# SVmitTreiber3LED2.net
KiCad netlist of a schematic drawn in EAGLE
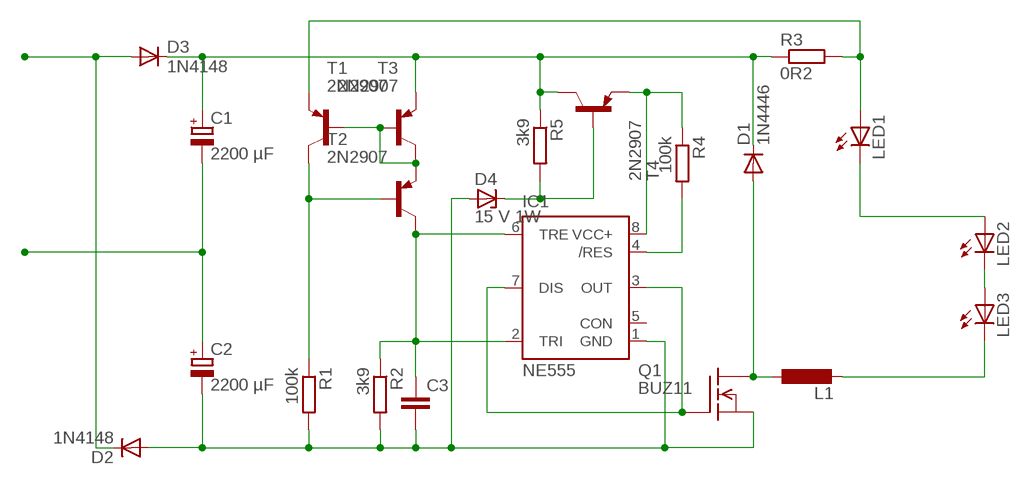
[diagram p0: schematic, sheet 1]

(export (version "E")
  (design (tool "Eeschema 10.0.6"))
  (components
    (comp (ref "C1")
      (value "2200 µF")
      (footprint "eagle-import:E5-10,5")
      (libsource (lib "eagle-import") (part "CPOL-EUE5-10.5"))
    )
    (comp (ref "C2")
      (value "2200 µF")
      (footprint "eagle-import:E5-10,5")
      (libsource (lib "eagle-import") (part "CPOL-EUE5-10.5"))
    )
    (comp (ref "C3")
      (value "C-EU025-024X044")
      (footprint "eagle-import:C025-024X044")
      (libsource (lib "eagle-import") (part "C-EU025-024X044"))
    )
    (comp (ref "D1")
      (value "1N4446")
      (footprint "eagle-import:DO35-10")
      (libsource (lib "eagle-import") (part "1N4446"))
    )
    (comp (ref "D2")
      (value "1N4148")
      (footprint "eagle-import:DO35-10")
      (libsource (lib "eagle-import") (part "1N4148DO35-10"))
    )
    (comp (ref "D3")
      (value "1N4148")
      (footprint "eagle-import:DO35-10")
      (libsource (lib "eagle-import") (part "1N4148DO35-10"))
    )
    (comp (ref "D4")
      (value "15 V 1W")
      (footprint "eagle-import:DO41Z10")
      (libsource (lib "eagle-import") (part "1N4728"))
    )
    (comp (ref "IC1")
      (value "NE555")
      (footprint "eagle-import:DIL-08")
      (fields (field (name "MF") "Arrow Electronics") (field (name "MPN") "NE555N"))
      (libsource (lib "eagle-import") (part "NE555"))
    )
    (comp (ref "L1")
      (value "L-EU6000-XXX-RC")
      (footprint "eagle-import:6000-XXXX-RC")
      (libsource (lib "eagle-import") (part "L-EU6000-XXX-RC"))
    )
    (comp (ref "LED1")
      (value "LED10MM")
      (footprint "eagle-import:LED10MM")
      (libsource (lib "eagle-import") (part "LED10MM"))
    )
    (comp (ref "LED2")
      (value "LED10MM")
      (footprint "eagle-import:LED10MM")
      (libsource (lib "eagle-import") (part "LED10MM"))
    )
    (comp (ref "LED3")
      (value "LED10MM")
      (footprint "eagle-import:LED10MM")
      (libsource (lib "eagle-import") (part "LED10MM"))
    )
    (comp (ref "Q1")
      (value "BUZ11")
      (footprint "eagle-import:TO220")
      (libsource (lib "eagle-import") (part "BUZ11"))
    )
    (comp (ref "R1")
      (value "100k")
      (footprint "eagle-import:0207_10")
      (libsource (lib "eagle-import") (part "R-EU_0207/10"))
    )
    (comp (ref "R2")
      (value "3k9")
      (footprint "eagle-import:0207_10")
      (libsource (lib "eagle-import") (part "R-EU_0207/10"))
    )
    (comp (ref "R3")
      (value "0R2")
      (footprint "eagle-import:0207_15")
      (libsource (lib "eagle-import") (part "R-EU_0207/15"))
    )
    (comp (ref "R4")
      (value "100k")
      (footprint "eagle-import:0207_10")
      (libsource (lib "eagle-import") (part "R-EU_0207/10"))
    )
    (comp (ref "R5")
      (value "3k9")
      (footprint "eagle-import:0207_10")
      (libsource (lib "eagle-import") (part "R-EU_0207/10"))
    )
    (comp (ref "T1")
      (value "2N2907")
      (footprint "eagle-import:TO18")
      (libsource (lib "eagle-import") (part "2N2907"))
    )
    (comp (ref "T2")
      (value "2N2907")
      (footprint "eagle-import:TO18")
      (libsource (lib "eagle-import") (part "2N2907"))
    )
    (comp (ref "T3")
      (value "2N2907")
      (footprint "eagle-import:TO18")
      (libsource (lib "eagle-import") (part "2N2907"))
    )
    (comp (ref "T4")
      (value "2N2907")
      (footprint "eagle-import:TO18")
      (libsource (lib "eagle-import") (part "2N2907"))
    )
  )
  (nets
    (net (code "1") (name "Net-(C1-Pad-)") (class "Default")
      (node (ref "C1") (pin "-") (pinfunction "-_-") (pintype "passive"))
      (node (ref "C2") (pin "+") (pinfunction "+_+") (pintype "passive"))
    )
    (net (code "2") (name "Net-(D2-PadC)") (class "Default")
      (node (ref "D2") (pin "C") (pinfunction "C_C") (pintype "passive"))
      (node (ref "D3") (pin "A") (pinfunction "A_A") (pintype "passive"))
    )
    (net (code "3") (name "Net-(IC1-DIS)") (class "Default")
      (node (ref "IC1") (pin "3") (pinfunction "OUT_3") (pintype "output"))
      (node (ref "IC1") (pin "7") (pinfunction "DIS_7") (pintype "input"))
      (node (ref "Q1") (pin "1") (pinfunction "G_1") (pintype "passive"))
    )
    (net (code "4") (name "Net-(IC1-GND)") (class "Default")
      (node (ref "C2") (pin "-") (pinfunction "-_-") (pintype "passive"))
      (node (ref "C3") (pin "2") (pinfunction "2_2") (pintype "passive"))
      (node (ref "D2") (pin "A") (pinfunction "A_A") (pintype "passive"))
      (node (ref "D4") (pin "A") (pinfunction "A_A") (pintype "passive"))
      (node (ref "IC1") (pin "1") (pinfunction "GND_1") (pintype "power_in"))
      (node (ref "Q1") (pin "3") (pinfunction "S_3") (pintype "passive"))
      (node (ref "R1") (pin "2") (pinfunction "2_2") (pintype "passive"))
      (node (ref "R2") (pin "2") (pinfunction "2_2") (pintype "passive"))
    )
    (net (code "5") (name "Net-(IC1-TRE)") (class "Default")
      (node (ref "C3") (pin "1") (pinfunction "1_1") (pintype "passive"))
      (node (ref "IC1") (pin "2") (pinfunction "TRI_2") (pintype "input"))
      (node (ref "IC1") (pin "6") (pinfunction "TRE_6") (pintype "input"))
      (node (ref "R2") (pin "1") (pinfunction "1_1") (pintype "passive"))
      (node (ref "T2") (pin "3") (pinfunction "C_3") (pintype "passive"))
    )
    (net (code "6") (name "Net-(IC1-VCC+)") (class "Default")
      (node (ref "IC1") (pin "8") (pinfunction "VCC+_8") (pintype "power_in"))
      (node (ref "R4") (pin "1") (pinfunction "1_1") (pintype "passive"))
      (node (ref "T4") (pin "1") (pinfunction "E_1") (pintype "passive"))
    )
    (net (code "7") (name "Net-(IC1-{slash}RES)") (class "Default")
      (node (ref "IC1") (pin "4") (pinfunction "/RES_4") (pintype "input"))
      (node (ref "R4") (pin "2") (pinfunction "2_2") (pintype "passive"))
    )
    (net (code "8") (name "Net-(LED1-C)") (class "Default")
      (node (ref "LED1") (pin "K") (pinfunction "C_K") (pintype "passive"))
      (node (ref "LED2") (pin "A") (pinfunction "A_A") (pintype "passive"))
    )
    (net (code "9") (name "Net-(LED2-C)") (class "Default")
      (node (ref "LED2") (pin "K") (pinfunction "C_K") (pintype "passive"))
      (node (ref "LED3") (pin "A") (pinfunction "A_A") (pintype "passive"))
    )
    (net (code "10") (name "Net-(LED3-C)") (class "Default")
      (node (ref "L1") (pin "2") (pinfunction "2_2") (pintype "passive"))
      (node (ref "LED3") (pin "K") (pinfunction "C_K") (pintype "passive"))
    )
    (net (code "11") (name "Net-(Q1-D)") (class "Default")
      (node (ref "D1") (pin "A") (pinfunction "A_A") (pintype "passive"))
      (node (ref "L1") (pin "1") (pinfunction "1_1") (pintype "passive"))
      (node (ref "Q1") (pin "2") (pinfunction "D_2") (pintype "passive"))
    )
    (net (code "12") (name "Net-(T1-B)") (class "Default")
      (node (ref "T1") (pin "2") (pinfunction "B_2") (pintype "passive"))
      (node (ref "T1") (pin "3") (pinfunction "C_3") (pintype "passive"))
      (node (ref "T2") (pin "1") (pinfunction "E_1") (pintype "passive"))
      (node (ref "T3") (pin "2") (pinfunction "B_2") (pintype "passive"))
    )
    (net (code "13") (name "Net-(T1-E)") (class "Default")
      (node (ref "C1") (pin "+") (pinfunction "+_+") (pintype "passive"))
      (node (ref "D1") (pin "C") (pinfunction "C_C") (pintype "passive"))
      (node (ref "D3") (pin "C") (pinfunction "C_C") (pintype "passive"))
      (node (ref "R3") (pin "1") (pinfunction "1_1") (pintype "passive"))
      (node (ref "R5") (pin "1") (pinfunction "1_1") (pintype "passive"))
      (node (ref "T1") (pin "1") (pinfunction "E_1") (pintype "passive"))
      (node (ref "T4") (pin "3") (pinfunction "C_3") (pintype "passive"))
    )
    (net (code "14") (name "Net-(T2-B)") (class "Default")
      (node (ref "R1") (pin "1") (pinfunction "1_1") (pintype "passive"))
      (node (ref "T2") (pin "2") (pinfunction "B_2") (pintype "passive"))
      (node (ref "T3") (pin "3") (pinfunction "C_3") (pintype "passive"))
    )
    (net (code "15") (name "Net-(T3-E)") (class "Default")
      (node (ref "LED1") (pin "A") (pinfunction "A_A") (pintype "passive"))
      (node (ref "R3") (pin "2") (pinfunction "2_2") (pintype "passive"))
      (node (ref "T3") (pin "1") (pinfunction "E_1") (pintype "passive"))
    )
    (net (code "16") (name "Net-(T4-B)") (class "Default")
      (node (ref "D4") (pin "C") (pinfunction "C_C") (pintype "passive"))
      (node (ref "R5") (pin "2") (pinfunction "2_2") (pintype "passive"))
      (node (ref "T4") (pin "2") (pinfunction "B_2") (pintype "passive"))
    )
    (net (code "17") (name "unconnected-(IC1-CON-Pad5)") (class "Default")
      (node (ref "IC1") (pin "5") (pinfunction "CON_5") (pintype "input"))
    )
  )
)
